# MotorBoard.net
KiCad netlist of a schematic drawn in EAGLE
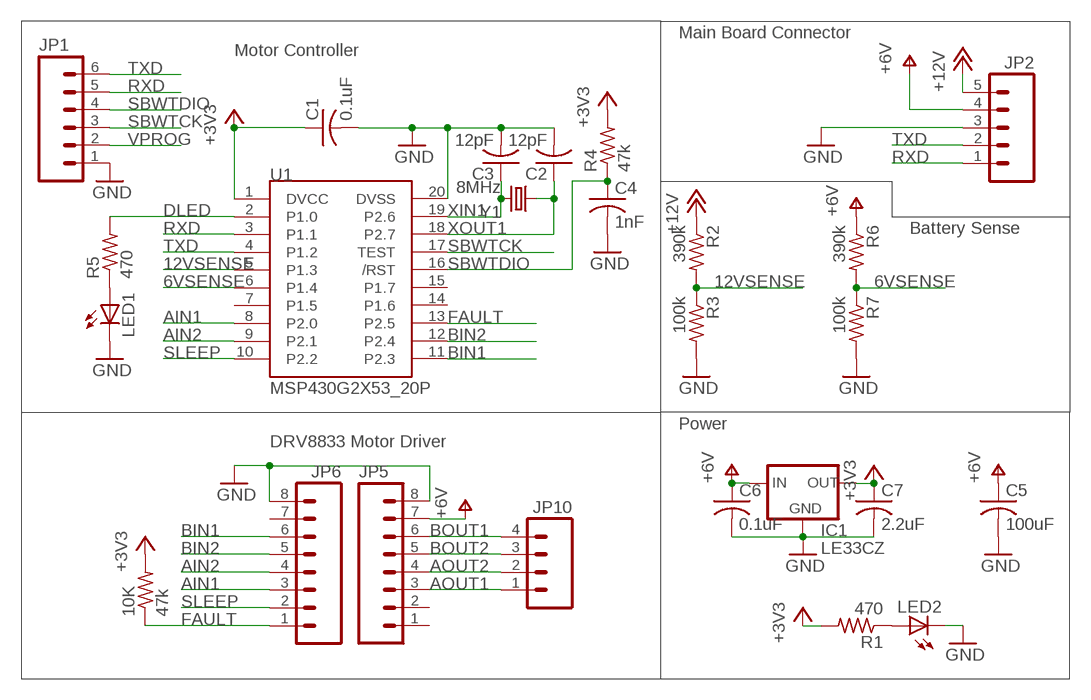
[diagram p0: schematic, sheet 1]

(export (version "E")
  (design (tool "Eeschema 10.0.6"))
  (components
    (comp (ref "10K")
      (value "47k")
      (footprint "eagle-import:R0805")
      (libsource (lib "eagle-import") (part "R-US_R0805"))
    )
    (comp (ref "C1")
      (value "0.1uF")
      (footprint "eagle-import:C0805")
      (libsource (lib "eagle-import") (part "C-USC0805"))
    )
    (comp (ref "C2")
      (value "12pF")
      (footprint "eagle-import:C0805")
      (libsource (lib "eagle-import") (part "C-USC0805"))
    )
    (comp (ref "C3")
      (value "12pF")
      (footprint "eagle-import:C0805")
      (libsource (lib "eagle-import") (part "C-USC0805"))
    )
    (comp (ref "C4")
      (value "1nF")
      (footprint "eagle-import:C0805")
      (libsource (lib "eagle-import") (part "C-USC0805"))
    )
    (comp (ref "C5")
      (value "100uF")
      (footprint "eagle-import:C0805")
      (libsource (lib "eagle-import") (part "C-USC0805"))
    )
    (comp (ref "C6")
      (value "0.1uF")
      (footprint "eagle-import:C0805")
      (libsource (lib "eagle-import") (part "C-USC0805"))
    )
    (comp (ref "C7")
      (value "2.2uF")
      (footprint "eagle-import:C0805")
      (libsource (lib "eagle-import") (part "C-USC0805"))
    )
    (comp (ref "IC1")
      (value "LE33CZ")
      (footprint "eagle-import:TO-92")
      (libsource (lib "eagle-import") (part "V_REG_78XXTO-92"))
    )
    (comp (ref "JP1")
      (value "M06SIP")
      (footprint "eagle-import:1X06")
      (libsource (lib "eagle-import") (part "M06SIP"))
    )
    (comp (ref "JP2")
      (value "M05PTH")
      (footprint "eagle-import:1X05")
      (libsource (lib "eagle-import") (part "M05PTH"))
    )
    (comp (ref "JP5")
      (value "M081X08")
      (footprint "eagle-import:1X08")
      (libsource (lib "eagle-import") (part "M081X08"))
    )
    (comp (ref "JP6")
      (value "M081X08")
      (footprint "eagle-import:1X08")
      (libsource (lib "eagle-import") (part "M081X08"))
    )
    (comp (ref "JP10")
      (value "M04PTH")
      (footprint "eagle-import:1X04")
      (libsource (lib "eagle-import") (part "M04PTH"))
    )
    (comp (ref "LED1")
      (value "LEDCHIP-LED0805")
      (footprint "eagle-import:CHIP-LED0805")
      (libsource (lib "eagle-import") (part "LEDCHIP-LED0805"))
    )
    (comp (ref "LED2")
      (value "LEDCHIP-LED0805")
      (footprint "eagle-import:CHIP-LED0805")
      (libsource (lib "eagle-import") (part "LEDCHIP-LED0805"))
    )
    (comp (ref "R1")
      (value "470")
      (footprint "eagle-import:R0805")
      (libsource (lib "eagle-import") (part "R-US_R0805"))
    )
    (comp (ref "R2")
      (value "390k")
      (footprint "eagle-import:R0805")
      (libsource (lib "eagle-import") (part "R-US_R0805"))
    )
    (comp (ref "R3")
      (value "100k")
      (footprint "eagle-import:R0805")
      (libsource (lib "eagle-import") (part "R-US_R0805"))
    )
    (comp (ref "R4")
      (value "47k")
      (footprint "eagle-import:R0805")
      (libsource (lib "eagle-import") (part "R-US_R0805"))
    )
    (comp (ref "R5")
      (value "470")
      (footprint "eagle-import:R0805")
      (libsource (lib "eagle-import") (part "R-US_R0805"))
    )
    (comp (ref "R6")
      (value "390k")
      (footprint "eagle-import:R0805")
      (libsource (lib "eagle-import") (part "R-US_R0805"))
    )
    (comp (ref "R7")
      (value "100k")
      (footprint "eagle-import:R0805")
      (libsource (lib "eagle-import") (part "R-US_R0805"))
    )
    (comp (ref "U1")
      (value "MSP430G2X53_20P")
      (footprint "eagle-import:TSSOP20_PW")
      (libsource (lib "eagle-import") (part "MSP430G2X53_20P"))
    )
    (comp (ref "Y1")
      (value "8MHz")
      (footprint "eagle-import:HC49U-V")
      (libsource (lib "eagle-import") (part "CRYSTALHC49UV"))
    )
  )
  (nets
    (net (code "1") (name "+3V3") (class "Default")
      (node (ref "10K") (pin "2") (pinfunction "2_2") (pintype "passive"))
      (node (ref "C1") (pin "1") (pinfunction "1_1") (pintype "passive"))
      (node (ref "C7") (pin "1") (pinfunction "1_1") (pintype "passive"))
      (node (ref "IC1") (pin "3") (pinfunction "OUT_3") (pintype "output"))
      (node (ref "R1") (pin "2") (pinfunction "2_2") (pintype "passive"))
      (node (ref "R4") (pin "2") (pinfunction "2_2") (pintype "passive"))
      (node (ref "U1") (pin "1") (pinfunction "DVCC_1") (pintype "bidirectional"))
    )
    (net (code "2") (name "+6V") (class "Default")
      (node (ref "C5") (pin "1") (pinfunction "1_1") (pintype "passive"))
      (node (ref "C6") (pin "1") (pinfunction "1_1") (pintype "passive"))
      (node (ref "IC1") (pin "2") (pinfunction "IN_2") (pintype "input"))
      (node (ref "JP2") (pin "4") (pinfunction "4_4") (pintype "passive"))
      (node (ref "JP5") (pin "7") (pinfunction "7_7") (pintype "passive"))
      (node (ref "R6") (pin "1") (pinfunction "1_1") (pintype "passive"))
    )
    (net (code "3") (name "+12V") (class "Default")
      (node (ref "JP2") (pin "5") (pinfunction "5_5") (pintype "passive"))
      (node (ref "R2") (pin "1") (pinfunction "1_1") (pintype "passive"))
    )
    (net (code "4") (name "/6VSENSE") (class "Default")
      (node (ref "R6") (pin "2") (pinfunction "2_2") (pintype "passive"))
      (node (ref "R7") (pin "1") (pinfunction "1_1") (pintype "passive"))
      (node (ref "U1") (pin "6") (pinfunction "P1.4_6") (pintype "bidirectional"))
    )
    (net (code "5") (name "/12VSENSE") (class "Default")
      (node (ref "R2") (pin "2") (pinfunction "2_2") (pintype "passive"))
      (node (ref "R3") (pin "1") (pinfunction "1_1") (pintype "passive"))
      (node (ref "U1") (pin "5") (pinfunction "P1.3_5") (pintype "bidirectional"))
    )
    (net (code "6") (name "/AIN1") (class "Default")
      (node (ref "JP6") (pin "3") (pinfunction "3_3") (pintype "passive"))
      (node (ref "U1") (pin "8") (pinfunction "P2.0_8") (pintype "bidirectional"))
    )
    (net (code "7") (name "/AIN2") (class "Default")
      (node (ref "JP6") (pin "4") (pinfunction "4_4") (pintype "passive"))
      (node (ref "U1") (pin "9") (pinfunction "P2.1_9") (pintype "bidirectional"))
    )
    (net (code "8") (name "/AOUT1") (class "Default")
      (node (ref "JP10") (pin "1") (pinfunction "1_1") (pintype "passive"))
      (node (ref "JP5") (pin "3") (pinfunction "3_3") (pintype "passive"))
    )
    (net (code "9") (name "/AOUT2") (class "Default")
      (node (ref "JP10") (pin "2") (pinfunction "2_2") (pintype "passive"))
      (node (ref "JP5") (pin "4") (pinfunction "4_4") (pintype "passive"))
    )
    (net (code "10") (name "/BIN1") (class "Default")
      (node (ref "JP6") (pin "6") (pinfunction "6_6") (pintype "passive"))
      (node (ref "U1") (pin "11") (pinfunction "P2.3_11") (pintype "bidirectional"))
    )
    (net (code "11") (name "/BIN2") (class "Default")
      (node (ref "JP6") (pin "5") (pinfunction "5_5") (pintype "passive"))
      (node (ref "U1") (pin "12") (pinfunction "P2.4_12") (pintype "bidirectional"))
    )
    (net (code "12") (name "/BOUT1") (class "Default")
      (node (ref "JP10") (pin "4") (pinfunction "4_4") (pintype "passive"))
      (node (ref "JP5") (pin "6") (pinfunction "6_6") (pintype "passive"))
    )
    (net (code "13") (name "/BOUT2") (class "Default")
      (node (ref "JP10") (pin "3") (pinfunction "3_3") (pintype "passive"))
      (node (ref "JP5") (pin "5") (pinfunction "5_5") (pintype "passive"))
    )
    (net (code "14") (name "/DLED") (class "Default")
      (node (ref "R5") (pin "2") (pinfunction "2_2") (pintype "passive"))
      (node (ref "U1") (pin "2") (pinfunction "P1.0_2") (pintype "bidirectional"))
    )
    (net (code "15") (name "/FAULT") (class "Default")
      (node (ref "10K") (pin "1") (pinfunction "1_1") (pintype "passive"))
      (node (ref "JP6") (pin "1") (pinfunction "1_1") (pintype "passive"))
      (node (ref "U1") (pin "13") (pinfunction "P2.5_13") (pintype "bidirectional"))
    )
    (net (code "16") (name "/RXD") (class "Default")
      (node (ref "JP1") (pin "5") (pinfunction "5_5") (pintype "passive"))
      (node (ref "JP2") (pin "1") (pinfunction "1_1") (pintype "passive"))
      (node (ref "U1") (pin "3") (pinfunction "P1.1_3") (pintype "bidirectional"))
    )
    (net (code "17") (name "/SBWTCK") (class "Default")
      (node (ref "JP1") (pin "3") (pinfunction "3_3") (pintype "passive"))
      (node (ref "U1") (pin "17") (pinfunction "TEST_17") (pintype "bidirectional"))
    )
    (net (code "18") (name "/SBWTDIO") (class "Default")
      (node (ref "C4") (pin "1") (pinfunction "1_1") (pintype "passive"))
      (node (ref "JP1") (pin "4") (pinfunction "4_4") (pintype "passive"))
      (node (ref "R4") (pin "1") (pinfunction "1_1") (pintype "passive"))
      (node (ref "U1") (pin "16") (pinfunction "/RST_16") (pintype "bidirectional"))
    )
    (net (code "19") (name "/SLEEP") (class "Default")
      (node (ref "JP6") (pin "2") (pinfunction "2_2") (pintype "passive"))
      (node (ref "U1") (pin "10") (pinfunction "P2.2_10") (pintype "bidirectional"))
    )
    (net (code "20") (name "/TXD") (class "Default")
      (node (ref "JP1") (pin "6") (pinfunction "6_6") (pintype "passive"))
      (node (ref "JP2") (pin "2") (pinfunction "2_2") (pintype "passive"))
      (node (ref "U1") (pin "4") (pinfunction "P1.2_4") (pintype "bidirectional"))
    )
    (net (code "21") (name "/VPROG") (class "Default")
      (node (ref "JP1") (pin "2") (pinfunction "2_2") (pintype "passive"))
    )
    (net (code "22") (name "/XIN1") (class "Default")
      (node (ref "C3") (pin "1") (pinfunction "1_1") (pintype "passive"))
      (node (ref "U1") (pin "19") (pinfunction "P2.6_19") (pintype "bidirectional"))
      (node (ref "Y1") (pin "2") (pinfunction "2_2") (pintype "passive"))
    )
    (net (code "23") (name "/XOUT1") (class "Default")
      (node (ref "C2") (pin "1") (pinfunction "1_1") (pintype "passive"))
      (node (ref "U1") (pin "18") (pinfunction "P2.7_18") (pintype "bidirectional"))
      (node (ref "Y1") (pin "1") (pinfunction "1_1") (pintype "passive"))
    )
    (net (code "24") (name "GND") (class "Default")
      (node (ref "C1") (pin "2") (pinfunction "2_2") (pintype "passive"))
      (node (ref "C2") (pin "2") (pinfunction "2_2") (pintype "passive"))
      (node (ref "C3") (pin "2") (pinfunction "2_2") (pintype "passive"))
      (node (ref "C4") (pin "2") (pinfunction "2_2") (pintype "passive"))
      (node (ref "C5") (pin "2") (pinfunction "2_2") (pintype "passive"))
      (node (ref "C6") (pin "2") (pinfunction "2_2") (pintype "passive"))
      (node (ref "C7") (pin "2") (pinfunction "2_2") (pintype "passive"))
      (node (ref "IC1") (pin "1") (pinfunction "GND_1") (pintype "input"))
      (node (ref "JP1") (pin "1") (pinfunction "1_1") (pintype "passive"))
      (node (ref "JP2") (pin "3") (pinfunction "3_3") (pintype "passive"))
      (node (ref "JP5") (pin "8") (pinfunction "8_8") (pintype "passive"))
      (node (ref "JP6") (pin "8") (pinfunction "8_8") (pintype "passive"))
      (node (ref "LED1") (pin "C") (pinfunction "C_C") (pintype "passive"))
      (node (ref "LED2") (pin "C") (pinfunction "C_C") (pintype "passive"))
      (node (ref "R3") (pin "2") (pinfunction "2_2") (pintype "passive"))
      (node (ref "R7") (pin "2") (pinfunction "2_2") (pintype "passive"))
      (node (ref "U1") (pin "20") (pinfunction "DVSS_20") (pintype "bidirectional"))
    )
    (net (code "25") (name "Net-(LED1-PadA)") (class "Default")
      (node (ref "LED1") (pin "A") (pinfunction "A_A") (pintype "passive"))
      (node (ref "R5") (pin "1") (pinfunction "1_1") (pintype "passive"))
    )
    (net (code "26") (name "Net-(LED2-PadA)") (class "Default")
      (node (ref "LED2") (pin "A") (pinfunction "A_A") (pintype "passive"))
      (node (ref "R1") (pin "1") (pinfunction "1_1") (pintype "passive"))
    )
    (net (code "27") (name "unconnected-(JP5-Pad1)") (class "Default")
      (node (ref "JP5") (pin "1") (pinfunction "1_1") (pintype "passive"))
    )
    (net (code "28") (name "unconnected-(JP5-Pad2)") (class "Default")
      (node (ref "JP5") (pin "2") (pinfunction "2_2") (pintype "passive"))
    )
    (net (code "29") (name "unconnected-(JP6-Pad7)") (class "Default")
      (node (ref "JP6") (pin "7") (pinfunction "7_7") (pintype "passive"))
    )
    (net (code "30") (name "unconnected-(U1-P1.5-Pad7)") (class "Default")
      (node (ref "U1") (pin "7") (pinfunction "P1.5_7") (pintype "bidirectional"))
    )
    (net (code "31") (name "unconnected-(U1-P1.6-Pad14)") (class "Default")
      (node (ref "U1") (pin "14") (pinfunction "P1.6_14") (pintype "bidirectional"))
    )
    (net (code "32") (name "unconnected-(U1-P1.7-Pad15)") (class "Default")
      (node (ref "U1") (pin "15") (pinfunction "P1.7_15") (pintype "bidirectional"))
    )
  )
)
